# gameglobe.net
KiCad netlist of a schematic drawn in EAGLE
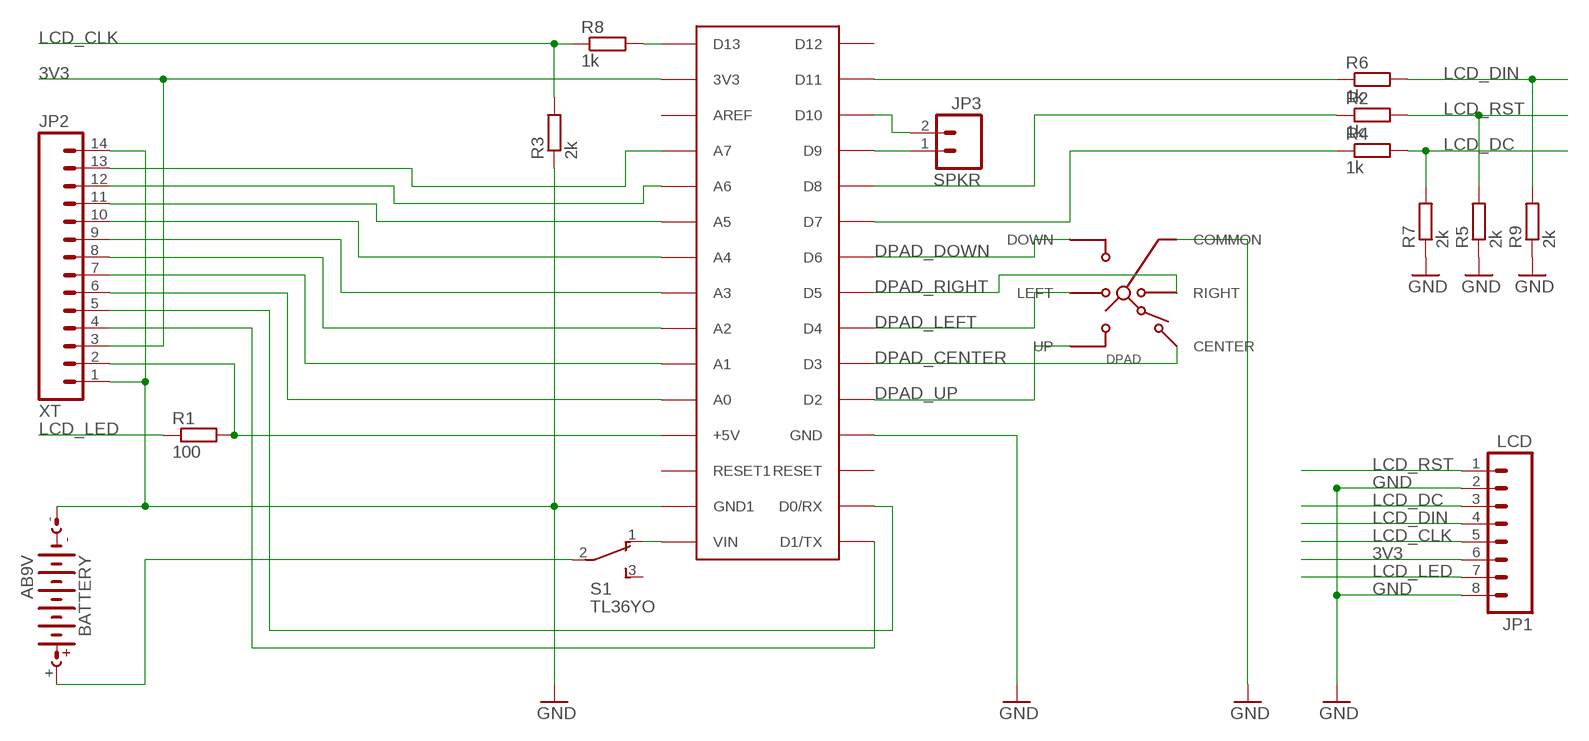
[diagram p0: schematic, sheet 1]

(export (version "E")
  (design (tool "Eeschema 10.0.6"))
  (components
    (comp (ref "ARDUINO_NANO")
      (value "ARDUINONANO")
      (footprint "eagle-import:PDIP-32")
      (libsource (lib "eagle-import") (part "ARDUINONANO"))
    )
    (comp (ref "BATTERY")
      (value "AB9V")
      (footprint "eagle-import:AB9V")
      (libsource (lib "eagle-import") (part "AB9V"))
    )
    (comp (ref "DPAD")
      (value "SKQUCAA010")
      (footprint "eagle-import:SKQU")
      (fields (field (name "MF") "ALPS"))
      (libsource (lib "eagle-import") (part "SKQUCAA010"))
    )
    (comp (ref "JP1")
      (value "LCD")
      (footprint "eagle-import:1X08_ROUND")
      (libsource (lib "eagle-import") (part "M08"))
    )
    (comp (ref "JP2")
      (value "XT")
      (footprint "eagle-import:1X14-LONGPADS")
      (libsource (lib "eagle-import") (part "M14LONGPADS"))
    )
    (comp (ref "JP3")
      (value "SPKR")
      (footprint "eagle-import:1X02")
      (libsource (lib "eagle-import") (part "M02PTH"))
    )
    (comp (ref "R1")
      (value "100")
      (footprint "eagle-import:0411_15")
      (libsource (lib "eagle-import") (part "R-EU_0411/15"))
    )
    (comp (ref "R2")
      (value "1k")
      (footprint "eagle-import:0411_15")
      (libsource (lib "eagle-import") (part "R-EU_0411/15"))
    )
    (comp (ref "R3")
      (value "2k")
      (footprint "eagle-import:0411_15")
      (libsource (lib "eagle-import") (part "R-EU_0411/15"))
    )
    (comp (ref "R4")
      (value "1k")
      (footprint "eagle-import:0411_15")
      (libsource (lib "eagle-import") (part "R-EU_0411/15"))
    )
    (comp (ref "R5")
      (value "2k")
      (footprint "eagle-import:0411_15")
      (libsource (lib "eagle-import") (part "R-EU_0411/15"))
    )
    (comp (ref "R6")
      (value "1k")
      (footprint "eagle-import:0411_15")
      (libsource (lib "eagle-import") (part "R-EU_0411/15"))
    )
    (comp (ref "R7")
      (value "2k")
      (footprint "eagle-import:0411_15")
      (libsource (lib "eagle-import") (part "R-EU_0411/15"))
    )
    (comp (ref "R8")
      (value "1k")
      (footprint "eagle-import:0411_15")
      (libsource (lib "eagle-import") (part "R-EU_0411/15"))
    )
    (comp (ref "R9")
      (value "2k")
      (footprint "eagle-import:0411_15")
      (libsource (lib "eagle-import") (part "R-EU_0411/15"))
    )
    (comp (ref "S1")
      (value "TL36YO")
      (footprint "eagle-import:TL3XYO")
      (libsource (lib "eagle-import") (part "TL36YO"))
    )
  )
  (nets
    (net (code "1") (name "/3V3") (class "Default")
      (node (ref "ARDUINO_NANO") (pin "3V3") (pinfunction "3V3_3V3") (pintype "bidirectional"))
      (node (ref "JP1") (pin "6") (pinfunction "6_6") (pintype "passive"))
      (node (ref "JP2") (pin "3") (pinfunction "3_3") (pintype "passive"))
    )
    (net (code "2") (name "/DPAD_CENTER") (class "Default")
      (node (ref "ARDUINO_NANO") (pin "D3") (pinfunction "D3_D3") (pintype "bidirectional"))
      (node (ref "DPAD") (pin "CENTER") (pinfunction "CENTER_CENTER") (pintype "passive"))
    )
    (net (code "3") (name "/DPAD_DOWN") (class "Default")
      (node (ref "ARDUINO_NANO") (pin "D6") (pinfunction "D6_D6") (pintype "bidirectional"))
      (node (ref "DPAD") (pin "DOWN") (pinfunction "DOWN_DOWN") (pintype "passive"))
    )
    (net (code "4") (name "/DPAD_LEFT") (class "Default")
      (node (ref "ARDUINO_NANO") (pin "D4") (pinfunction "D4_D4") (pintype "bidirectional"))
      (node (ref "DPAD") (pin "LEFT") (pinfunction "LEFT_LEFT") (pintype "passive"))
    )
    (net (code "5") (name "/DPAD_RIGHT") (class "Default")
      (node (ref "ARDUINO_NANO") (pin "D5") (pinfunction "D5_D5") (pintype "bidirectional"))
      (node (ref "DPAD") (pin "RIGHT") (pinfunction "RIGHT_RIGHT") (pintype "passive"))
    )
    (net (code "6") (name "/DPAD_UP") (class "Default")
      (node (ref "ARDUINO_NANO") (pin "D2") (pinfunction "D2_D2") (pintype "bidirectional"))
      (node (ref "DPAD") (pin "UP") (pinfunction "UP_UP") (pintype "passive"))
    )
    (net (code "7") (name "/LCD_CLK") (class "Default")
      (node (ref "JP1") (pin "5") (pinfunction "5_5") (pintype "passive"))
      (node (ref "R3") (pin "2") (pinfunction "2_2") (pintype "passive"))
      (node (ref "R8") (pin "1") (pinfunction "1_1") (pintype "passive"))
    )
    (net (code "8") (name "/LCD_DC") (class "Default")
      (node (ref "JP1") (pin "3") (pinfunction "3_3") (pintype "passive"))
      (node (ref "R4") (pin "2") (pinfunction "2_2") (pintype "passive"))
      (node (ref "R7") (pin "2") (pinfunction "2_2") (pintype "passive"))
    )
    (net (code "9") (name "/LCD_DIN") (class "Default")
      (node (ref "JP1") (pin "4") (pinfunction "4_4") (pintype "passive"))
      (node (ref "R6") (pin "2") (pinfunction "2_2") (pintype "passive"))
      (node (ref "R9") (pin "2") (pinfunction "2_2") (pintype "passive"))
    )
    (net (code "10") (name "/LCD_LED") (class "Default")
      (node (ref "JP1") (pin "7") (pinfunction "7_7") (pintype "passive"))
      (node (ref "R1") (pin "1") (pinfunction "1_1") (pintype "passive"))
    )
    (net (code "11") (name "/LCD_RST") (class "Default")
      (node (ref "JP1") (pin "1") (pinfunction "1_1") (pintype "passive"))
      (node (ref "R2") (pin "2") (pinfunction "2_2") (pintype "passive"))
      (node (ref "R5") (pin "2") (pinfunction "2_2") (pintype "passive"))
    )
    (net (code "12") (name "GND") (class "Default")
      (node (ref "ARDUINO_NANO") (pin "GND") (pinfunction "GND_GND") (pintype "bidirectional"))
      (node (ref "ARDUINO_NANO") (pin "GND1") (pinfunction "GND1_GND1") (pintype "bidirectional"))
      (node (ref "BATTERY") (pin "-") (pinfunction "-_-") (pintype "passive"))
      (node (ref "DPAD") (pin "COMMON") (pinfunction "COMMON_COMMON") (pintype "power_in"))
      (node (ref "JP1") (pin "2") (pinfunction "2_2") (pintype "passive"))
      (node (ref "JP1") (pin "8") (pinfunction "8_8") (pintype "passive"))
      (node (ref "JP2") (pin "1") (pinfunction "1_1") (pintype "passive"))
      (node (ref "JP2") (pin "14") (pinfunction "14_14") (pintype "passive"))
      (node (ref "R3") (pin "1") (pinfunction "1_1") (pintype "passive"))
      (node (ref "R5") (pin "1") (pinfunction "1_1") (pintype "passive"))
      (node (ref "R7") (pin "1") (pinfunction "1_1") (pintype "passive"))
      (node (ref "R9") (pin "1") (pinfunction "1_1") (pintype "passive"))
    )
    (net (code "13") (name "Net-(ARDUINO_NANO-Pad+5V)") (class "Default")
      (node (ref "ARDUINO_NANO") (pin "+5V") (pinfunction "+5V_+5V") (pintype "bidirectional"))
      (node (ref "JP2") (pin "2") (pinfunction "2_2") (pintype "passive"))
      (node (ref "R1") (pin "2") (pinfunction "2_2") (pintype "passive"))
    )
    (net (code "14") (name "Net-(ARDUINO_NANO-PadA0)") (class "Default")
      (node (ref "ARDUINO_NANO") (pin "A0") (pinfunction "A0_A0") (pintype "bidirectional"))
      (node (ref "JP2") (pin "6") (pinfunction "6_6") (pintype "passive"))
    )
    (net (code "15") (name "Net-(ARDUINO_NANO-PadA1)") (class "Default")
      (node (ref "ARDUINO_NANO") (pin "A1") (pinfunction "A1_A1") (pintype "bidirectional"))
      (node (ref "JP2") (pin "7") (pinfunction "7_7") (pintype "passive"))
    )
    (net (code "16") (name "Net-(ARDUINO_NANO-PadA2)") (class "Default")
      (node (ref "ARDUINO_NANO") (pin "A2") (pinfunction "A2_A2") (pintype "bidirectional"))
      (node (ref "JP2") (pin "8") (pinfunction "8_8") (pintype "passive"))
    )
    (net (code "17") (name "Net-(ARDUINO_NANO-PadA3)") (class "Default")
      (node (ref "ARDUINO_NANO") (pin "A3") (pinfunction "A3_A3") (pintype "bidirectional"))
      (node (ref "JP2") (pin "9") (pinfunction "9_9") (pintype "passive"))
    )
    (net (code "18") (name "Net-(ARDUINO_NANO-PadA4)") (class "Default")
      (node (ref "ARDUINO_NANO") (pin "A4") (pinfunction "A4_A4") (pintype "bidirectional"))
      (node (ref "JP2") (pin "10") (pinfunction "10_10") (pintype "passive"))
    )
    (net (code "19") (name "Net-(ARDUINO_NANO-PadA5)") (class "Default")
      (node (ref "ARDUINO_NANO") (pin "A5") (pinfunction "A5_A5") (pintype "bidirectional"))
      (node (ref "JP2") (pin "11") (pinfunction "11_11") (pintype "passive"))
    )
    (net (code "20") (name "Net-(ARDUINO_NANO-PadA6)") (class "Default")
      (node (ref "ARDUINO_NANO") (pin "A6") (pinfunction "A6_A6") (pintype "bidirectional"))
      (node (ref "JP2") (pin "12") (pinfunction "12_12") (pintype "passive"))
    )
    (net (code "21") (name "Net-(ARDUINO_NANO-PadA7)") (class "Default")
      (node (ref "ARDUINO_NANO") (pin "A7") (pinfunction "A7_A7") (pintype "bidirectional"))
      (node (ref "JP2") (pin "13") (pinfunction "13_13") (pintype "passive"))
    )
    (net (code "22") (name "Net-(ARDUINO_NANO-PadD0{slash}RX)") (class "Default")
      (node (ref "ARDUINO_NANO") (pin "D0/RX") (pinfunction "D0/RX_D0/RX") (pintype "bidirectional"))
      (node (ref "JP2") (pin "5") (pinfunction "5_5") (pintype "passive"))
    )
    (net (code "23") (name "Net-(ARDUINO_NANO-PadD1{slash}TX)") (class "Default")
      (node (ref "ARDUINO_NANO") (pin "D1/TX") (pinfunction "D1/TX_D1/TX") (pintype "bidirectional"))
      (node (ref "JP2") (pin "4") (pinfunction "4_4") (pintype "passive"))
    )
    (net (code "24") (name "Net-(ARDUINO_NANO-PadD7)") (class "Default")
      (node (ref "ARDUINO_NANO") (pin "D7") (pinfunction "D7_D7") (pintype "bidirectional"))
      (node (ref "R4") (pin "1") (pinfunction "1_1") (pintype "passive"))
    )
    (net (code "25") (name "Net-(ARDUINO_NANO-PadD8)") (class "Default")
      (node (ref "ARDUINO_NANO") (pin "D8") (pinfunction "D8_D8") (pintype "bidirectional"))
      (node (ref "R2") (pin "1") (pinfunction "1_1") (pintype "passive"))
    )
    (net (code "26") (name "Net-(ARDUINO_NANO-PadD9)") (class "Default")
      (node (ref "ARDUINO_NANO") (pin "D9") (pinfunction "D9_D9") (pintype "bidirectional"))
      (node (ref "JP3") (pin "1") (pinfunction "1_1") (pintype "passive"))
    )
    (net (code "27") (name "Net-(ARDUINO_NANO-PadD10)") (class "Default")
      (node (ref "ARDUINO_NANO") (pin "D10") (pinfunction "D10_D10") (pintype "bidirectional"))
      (node (ref "JP3") (pin "2") (pinfunction "2_2") (pintype "passive"))
    )
    (net (code "28") (name "Net-(ARDUINO_NANO-PadD11)") (class "Default")
      (node (ref "ARDUINO_NANO") (pin "D11") (pinfunction "D11_D11") (pintype "bidirectional"))
      (node (ref "R6") (pin "1") (pinfunction "1_1") (pintype "passive"))
    )
    (net (code "29") (name "Net-(ARDUINO_NANO-PadD13)") (class "Default")
      (node (ref "ARDUINO_NANO") (pin "D13") (pinfunction "D13_D13") (pintype "bidirectional"))
      (node (ref "R8") (pin "2") (pinfunction "2_2") (pintype "passive"))
    )
    (net (code "30") (name "Net-(S1-O)") (class "Default")
      (node (ref "ARDUINO_NANO") (pin "VIN") (pinfunction "VIN_VIN") (pintype "bidirectional"))
      (node (ref "S1") (pin "1") (pinfunction "O_1") (pintype "passive"))
    )
    (net (code "31") (name "Net-(S1-P)") (class "Default")
      (node (ref "BATTERY") (pin "+") (pinfunction "+_+") (pintype "passive"))
      (node (ref "S1") (pin "2") (pinfunction "P_2") (pintype "passive"))
    )
    (net (code "32") (name "unconnected-(ARDUINO_NANO-PadAREF)") (class "Default")
      (node (ref "ARDUINO_NANO") (pin "AREF") (pinfunction "AREF_AREF") (pintype "bidirectional"))
    )
    (net (code "33") (name "unconnected-(ARDUINO_NANO-PadD12)") (class "Default")
      (node (ref "ARDUINO_NANO") (pin "D12") (pinfunction "D12_D12") (pintype "bidirectional"))
    )
    (net (code "34") (name "unconnected-(ARDUINO_NANO-PadRESET)") (class "Default")
      (node (ref "ARDUINO_NANO") (pin "RESET") (pinfunction "RESET_RESET") (pintype "bidirectional"))
    )
    (net (code "35") (name "unconnected-(ARDUINO_NANO-PadRESET1)") (class "Default")
      (node (ref "ARDUINO_NANO") (pin "RESET1") (pinfunction "RESET1_RESET1") (pintype "bidirectional"))
    )
    (net (code "36") (name "unconnected-(S1-S-Pad3)") (class "Default")
      (node (ref "S1") (pin "3") (pinfunction "S_3") (pintype "passive"))
    )
  )
)
